# buckler.net
KiCad netlist of a schematic drawn in EAGLE
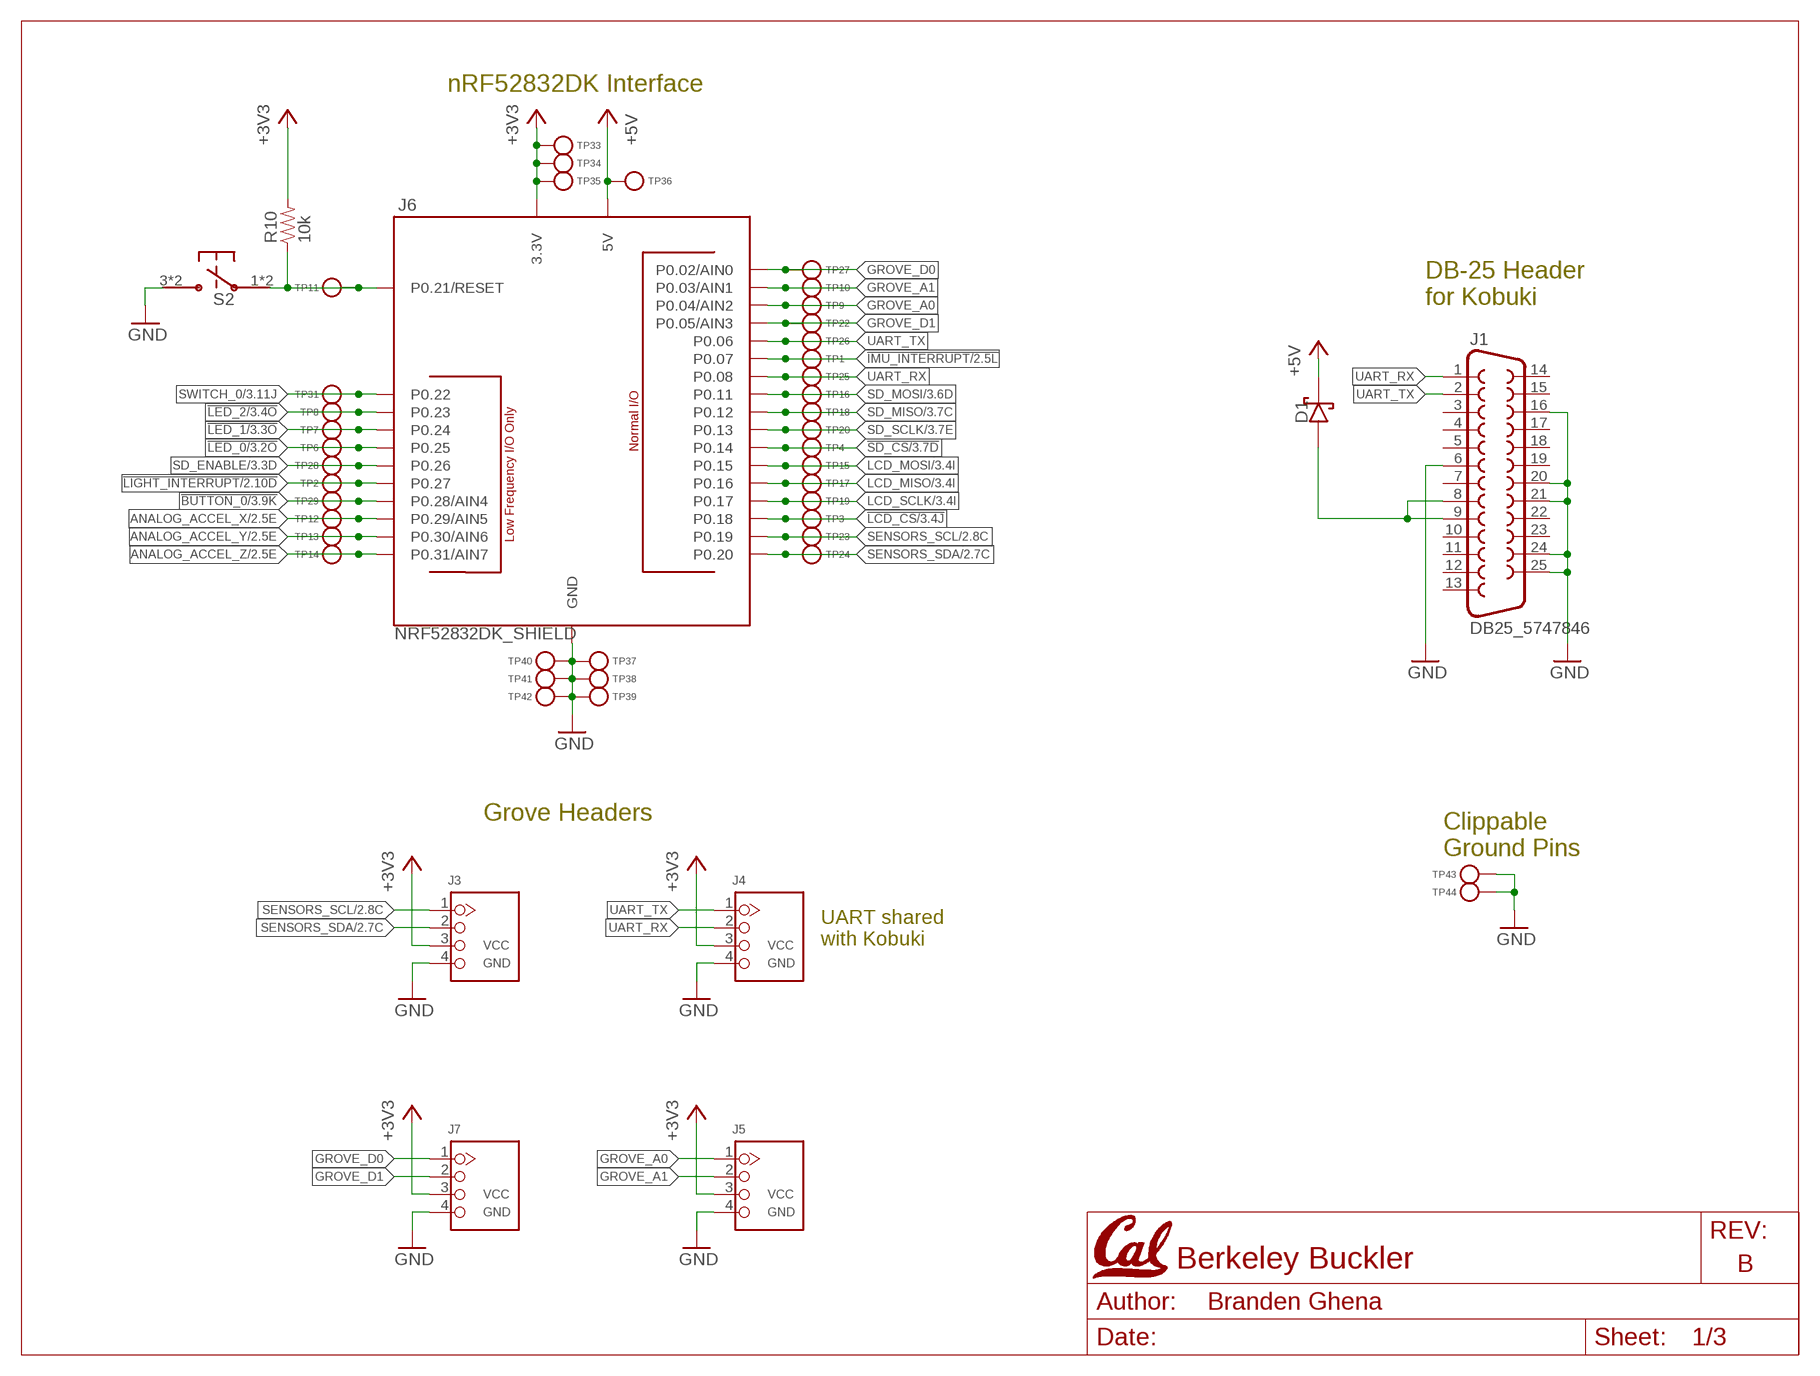
[diagram p0: schematic, sheet 1]
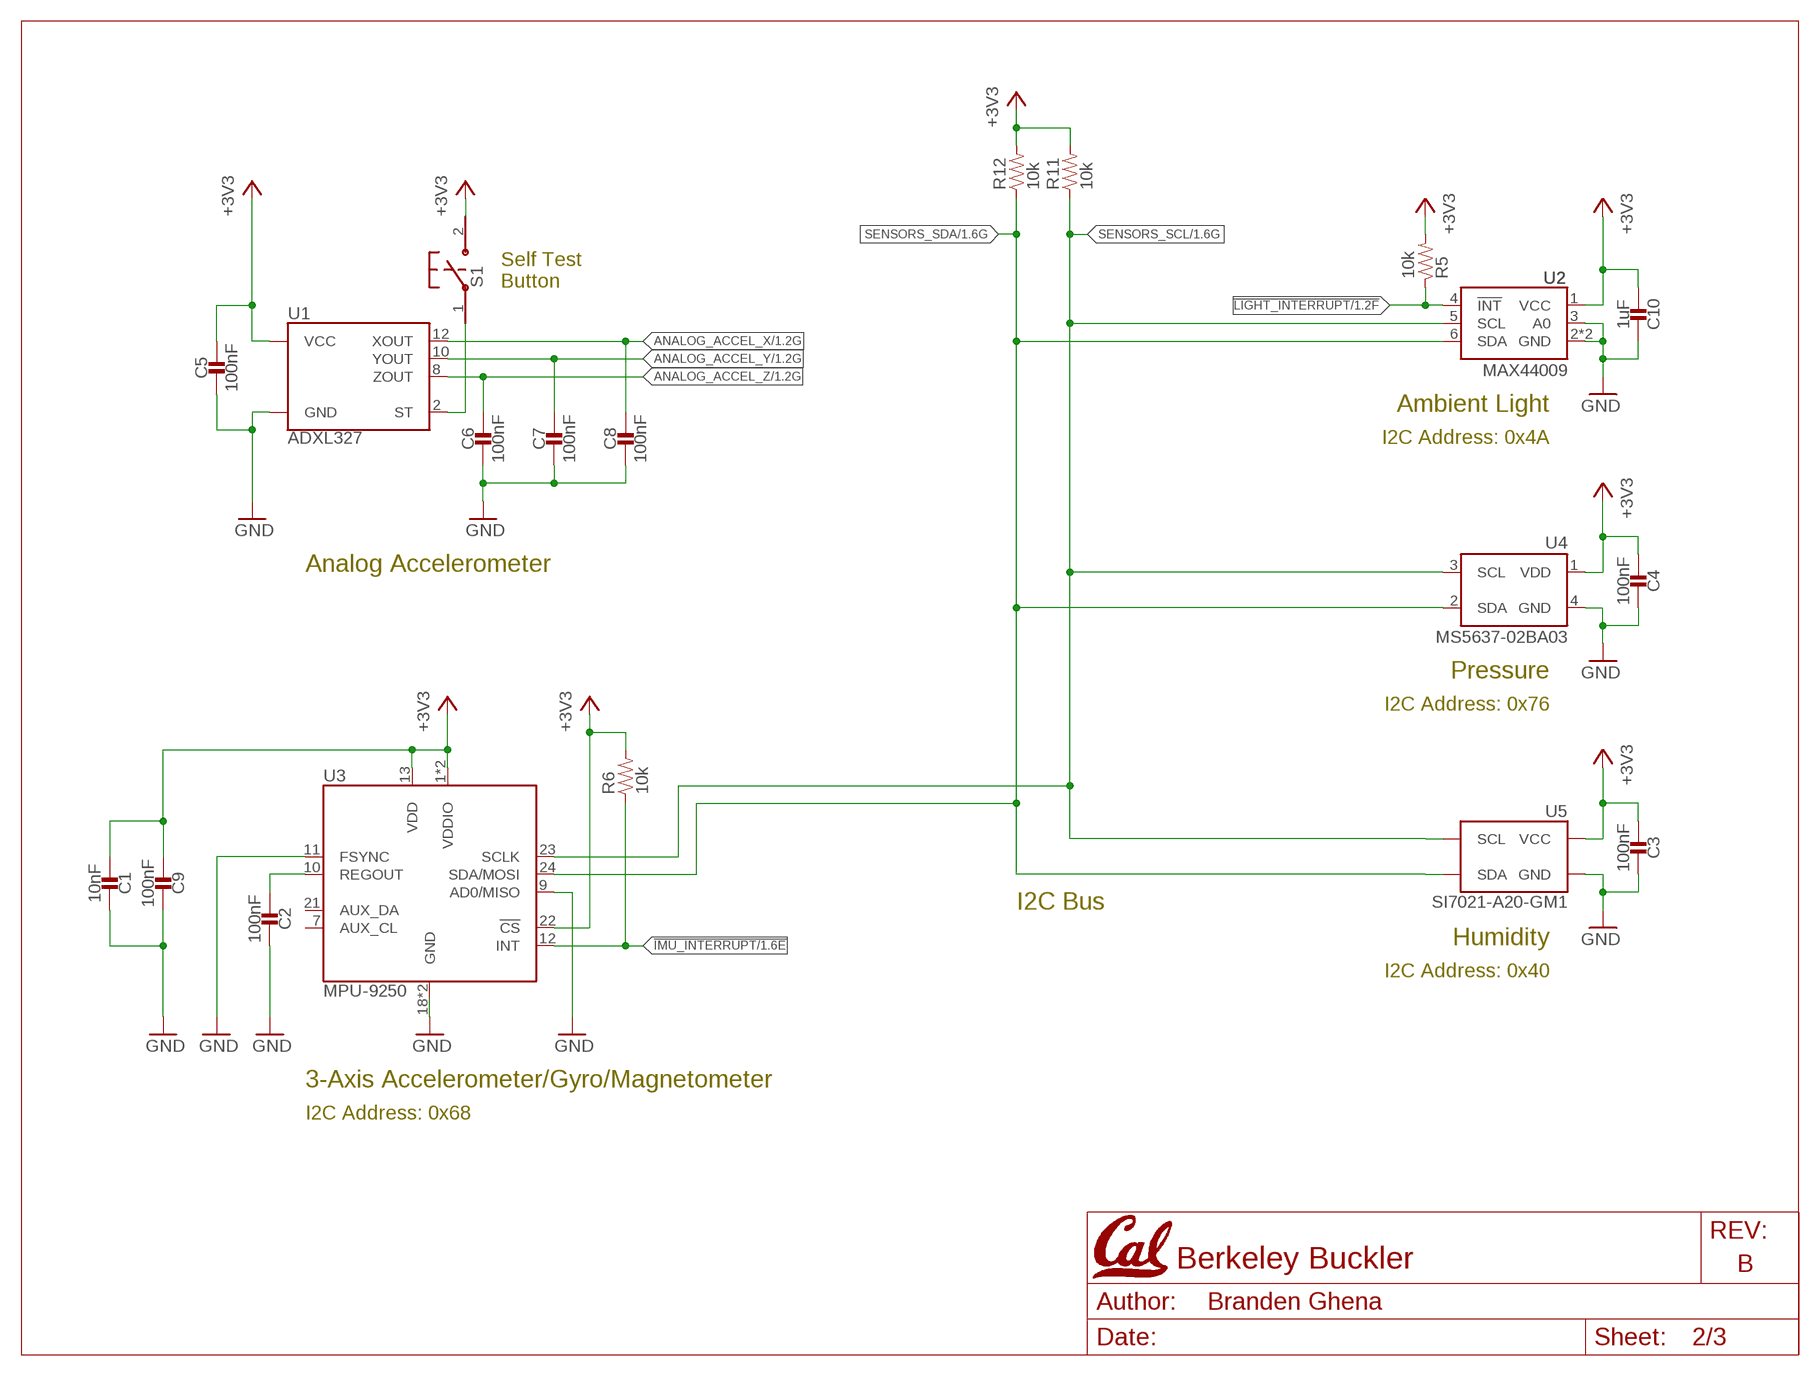
[diagram p1: schematic, sheet 2]
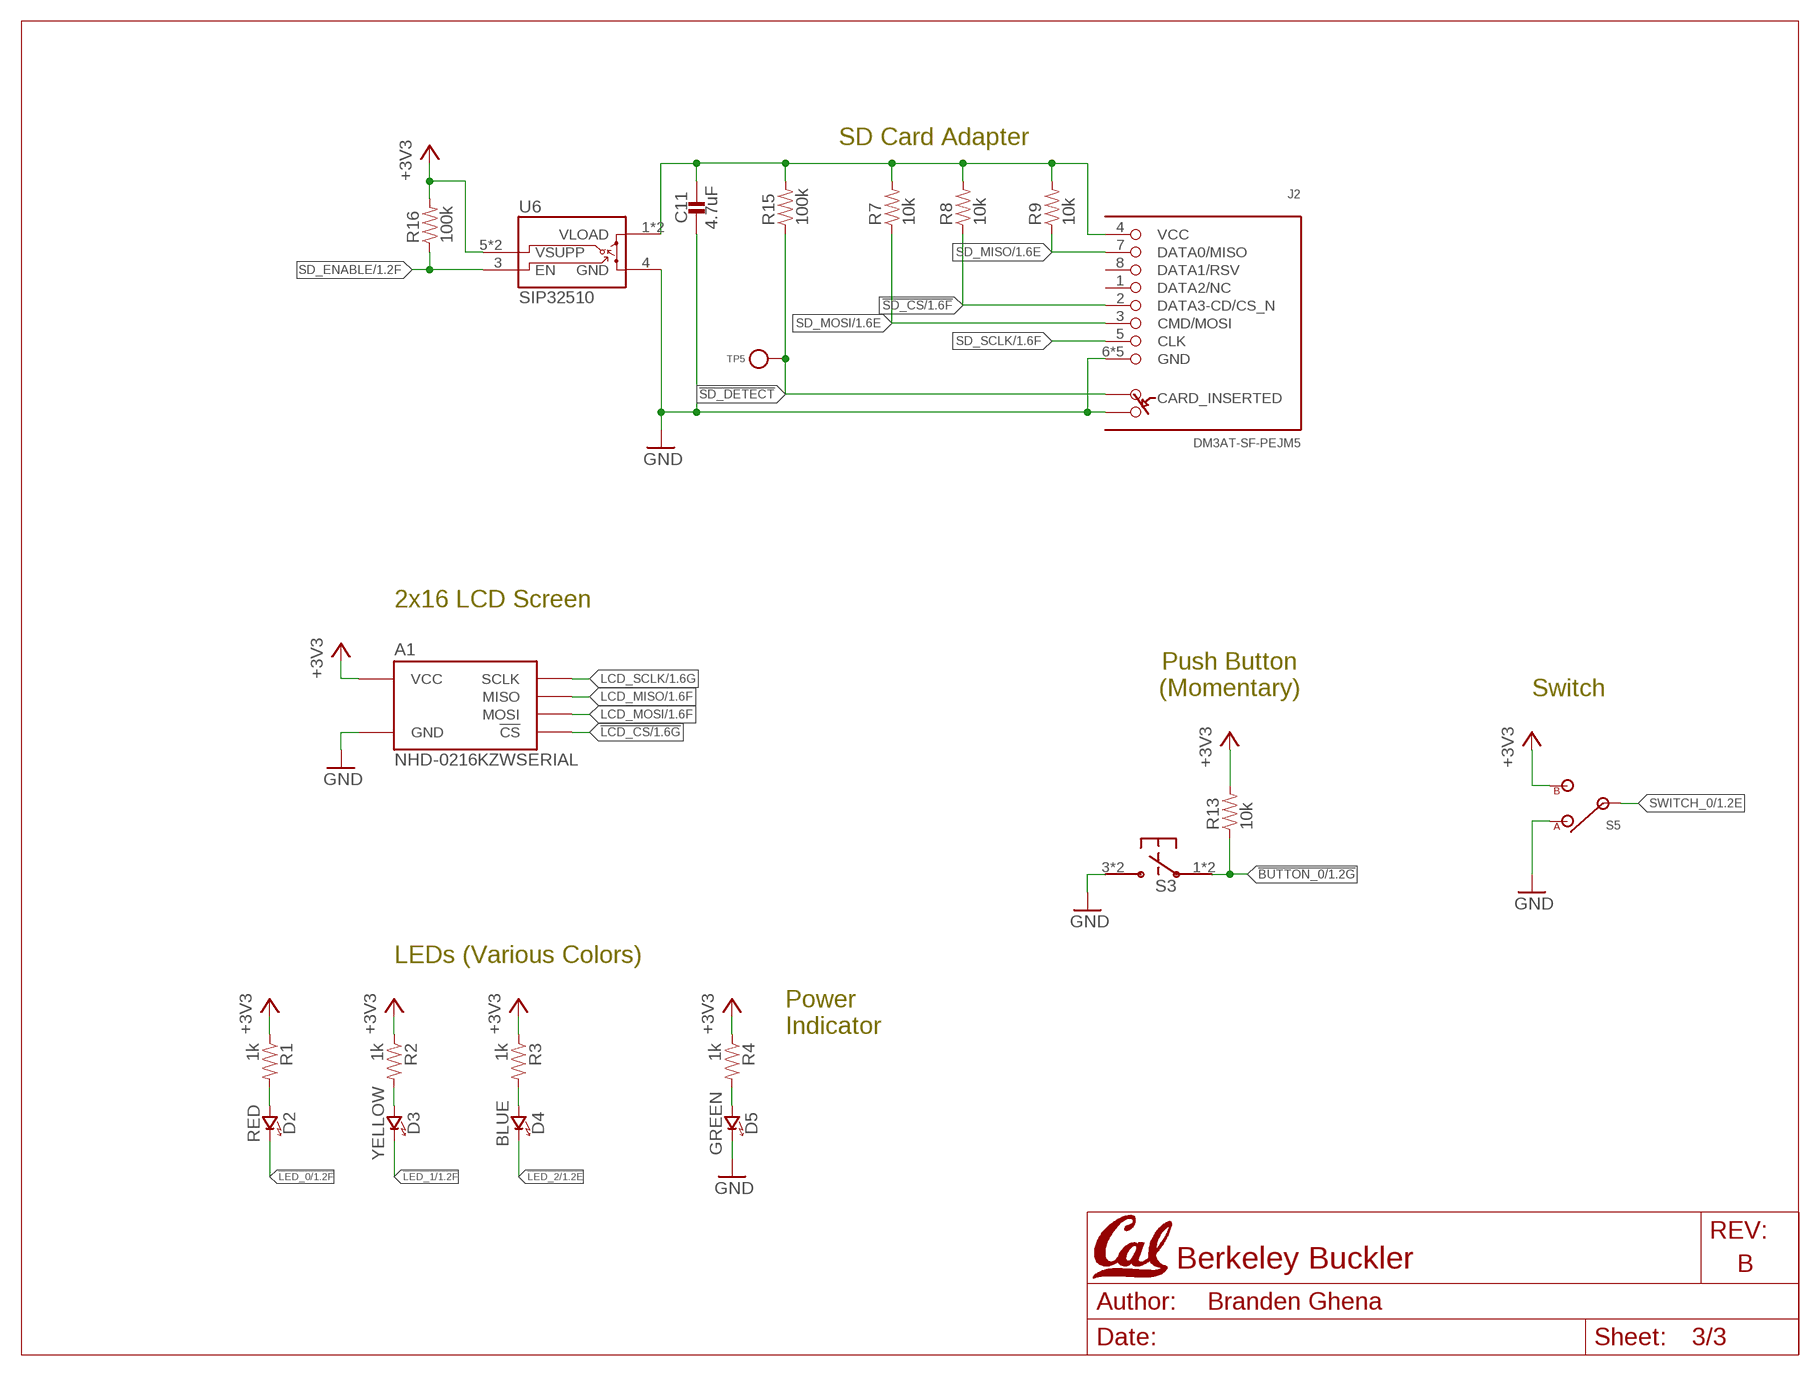
[diagram p2: schematic, sheet 3]

(export (version "E")
  (design (tool "Eeschema 10.0.6"))
  (components
    (comp (ref "C1")
      (value "10nF")
      (footprint "eagle-import:0402_CAP")
      (description "CAP CER 10000PF 25V X7R 0402")
      (fields (field (name "MANUFACTURER") "KEMET") (field (name "MPN") "C0402C103J3RACTU"))
      (libsource (lib "eagle-import") (part "CAPACITOR0402_CAP"))
    )
    (comp (ref "C2")
      (value "100nF")
      (footprint "eagle-import:0402_CAP")
      (description "CAP CER 0.1UF 16V X7R 0402")
      (fields (field (name "MANUFACTURER") "Murata") (field (name "MPN") "GCM155R71C104KA55D"))
      (libsource (lib "eagle-import") (part "CAPACITOR0402_CAP"))
    )
    (comp (ref "C3")
      (value "100nF")
      (footprint "eagle-import:0402_CAP")
      (description "CAP CER 0.1UF 16V X7R 0402")
      (fields (field (name "MANUFACTURER") "Murata") (field (name "MPN") "GCM155R71C104KA55D"))
      (libsource (lib "eagle-import") (part "CAPACITOR0402_CAP"))
    )
    (comp (ref "C4")
      (value "100nF")
      (footprint "eagle-import:0402_CAP")
      (description "CAP CER 0.1UF 16V X7R 0402")
      (fields (field (name "MANUFACTURER") "Murata") (field (name "MPN") "GCM155R71C104KA55D"))
      (libsource (lib "eagle-import") (part "CAPACITOR0402_CAP"))
    )
    (comp (ref "C5")
      (value "100nF")
      (footprint "eagle-import:0402_CAP")
      (description "CAP CER 0.1UF 16V X7R 0402")
      (fields (field (name "MANUFACTURER") "Murata") (field (name "MPN") "GCM155R71C104KA55D"))
      (libsource (lib "eagle-import") (part "CAPACITOR0402_CAP"))
    )
    (comp (ref "C6")
      (value "100nF")
      (footprint "eagle-import:0402_CAP")
      (description "CAP CER 0.1UF 16V X7R 0402")
      (fields (field (name "MANUFACTURER") "Murata") (field (name "MPN") "GCM155R71C104KA55D"))
      (libsource (lib "eagle-import") (part "CAPACITOR0402_CAP"))
    )
    (comp (ref "C7")
      (value "100nF")
      (footprint "eagle-import:0402_CAP")
      (description "CAP CER 0.1UF 16V X7R 0402")
      (fields (field (name "MANUFACTURER") "Murata") (field (name "MPN") "GCM155R71C104KA55D"))
      (libsource (lib "eagle-import") (part "CAPACITOR0402_CAP"))
    )
    (comp (ref "C8")
      (value "100nF")
      (footprint "eagle-import:0402_CAP")
      (description "CAP CER 0.1UF 16V X7R 0402")
      (fields (field (name "MANUFACTURER") "Murata") (field (name "MPN") "GCM155R71C104KA55D"))
      (libsource (lib "eagle-import") (part "CAPACITOR0402_CAP"))
    )
    (comp (ref "C9")
      (value "100nF")
      (footprint "eagle-import:0402_CAP")
      (description "CAP CER 0.1UF 16V X7R 0402")
      (fields (field (name "MANUFACTURER") "Murata") (field (name "MPN") "GCM155R71C104KA55D"))
      (libsource (lib "eagle-import") (part "CAPACITOR0402_CAP"))
    )
    (comp (ref "C10")
      (value "1uF")
      (footprint "eagle-import:0402_CAP")
      (description "CAP CER 1UF 10V X6S 0402")
      (fields
        (field (name "MANUFACTURER") "Samsung Electro-Mechanics")
        (field (name "MPN") "CL05X105KP5NNNC")
      )
      (libsource (lib "eagle-import") (part "CAPACITOR0402_CAP"))
    )
    (comp (ref "R5")
      (value "10k")
      (footprint "eagle-import:0402_RES")
      (description "RES SMD 10K OHM 1% 1/16W 0402")
      (fields (field (name "MANUFACTURER") "Samsung Electro-Mechanics") (field (name "MPN") "RC1005F103CS"))
      (libsource (lib "eagle-import") (part "RESISTOR0402_RES"))
    )
    (comp (ref "R6")
      (value "10k")
      (footprint "eagle-import:0402_RES")
      (description "RES SMD 10K OHM 1% 1/16W 0402")
      (fields (field (name "MANUFACTURER") "Samsung Electro-Mechanics") (field (name "MPN") "RC1005F103CS"))
      (libsource (lib "eagle-import") (part "RESISTOR0402_RES"))
    )
    (comp (ref "R11")
      (value "10k")
      (footprint "eagle-import:0402_RES")
      (description "RES SMD 10K OHM 1% 1/16W 0402")
      (fields (field (name "MANUFACTURER") "Samsung Electro-Mechanics") (field (name "MPN") "RC1005F103CS"))
      (libsource (lib "eagle-import") (part "RESISTOR0402_RES"))
    )
    (comp (ref "R12")
      (value "10k")
      (footprint "eagle-import:0402_RES")
      (description "RES SMD 10K OHM 1% 1/16W 0402")
      (fields (field (name "MANUFACTURER") "Samsung Electro-Mechanics") (field (name "MPN") "RC1005F103CS"))
      (libsource (lib "eagle-import") (part "RESISTOR0402_RES"))
    )
    (comp (ref "S1")
      (value "B3U-1000P")
      (footprint "eagle-import:B3U-1000P")
      (description "SWITCH TACTILE SPST-NO 0.05A 12V")
      (fields (field (name "MANUFACTURER") "Omron") (field (name "MPN") "B3U-1000P"))
      (libsource (lib "eagle-import") (part "B3U-1000P"))
    )
    (comp (ref "U1")
      (value "ADXL327")
      (footprint "eagle-import:LFCSP-16")
      (description "ACCELEROMETER 2G ANALOG 16LFCSP")
      (fields (field (name "MANUFACTURER") "Analog Devices Inc.") (field (name "MPN") "ADXL327BCPZ"))
      (libsource (lib "eagle-import") (part "ADXL327"))
    )
    (comp (ref "U2")
      (value "MAX44009")
      (footprint "eagle-import:UDFN-6-EXPOSED")
      (description "SENSOR AMBIENT LIGHT 6UTDFN")
      (fields
        (field (name "MANUFACTURER") "MAXIM")
        (field (name "MPN") "MAX44009EDT+T")
        (field (name "MANUFACTURER_1") "Maxim Integrated")
      )
      (libsource (lib "eagle-import") (part "MAX44009"))
    )
    (comp (ref "U3")
      (value "MPU-9250")
      (footprint "eagle-import:QFN-24_3MM")
      (description "IMU ACCEL/GYRO/MAG I2C/SPI 24QFN")
      (fields (field (name "MANUFACTURER") "TDK InvenSense"))
      (libsource (lib "eagle-import") (part "MPU-9250"))
    )
    (comp (ref "U4")
      (value "MS5637-02BA03")
      (footprint "eagle-import:4-SMD")
      (description "SENSOR 17.4PSIA I2C 24B 4-QFN")
      (fields (field (name "MANUFACTURER") "TE CONNECTIVITY") (field (name "MPN") "MS563702BA03-50"))
      (libsource (lib "eagle-import") (part "MS5637-02BA03"))
    )
    (comp (ref "U5")
      (value "SI7021-A20-GM1")
      (footprint "eagle-import:DFN-6_3MM")
      (description "SENS HUMI/TEMP 3.6V I2C 3% 6DFN")
      (fields (field (name "MANUFACTURER") "Silicon Labs") (field (name "MPN") "SI7021-A20-GM1 "))
      (libsource (lib "eagle-import") (part "SI7021-A20-GM1"))
    )
    (comp (ref "D1")
      (value "DIODE_SCHOTTKYSOD323")
      (footprint "eagle-import:SOD323")
      (description "DIODE SCHOTTKY 30V 500MA SOD323")
      (fields (field (name "MANUFACTURER") "Diodes Incorporated") (field (name "MPN") "B0530WS-7-F"))
      (libsource (lib "eagle-import") (part "DIODE_SCHOTTKYSOD323"))
    )
    (comp (ref "J1")
      (value "DB25_5747846")
      (footprint "eagle-import:DB25_5747846")
      (description "CONN D-SUB RCPT 25POS R/A SOLDER")
      (fields (field (name "MANUFACTURER") "TE Connectivity AMP Connectors") (field (name "MPN") "5747846-4"))
      (libsource (lib "eagle-import") (part "DB25_5747846"))
    )
    (comp (ref "J3")
      (value "4P-2.0")
      (footprint "eagle-import:HW4-2.0")
      (description "Grove - Universal 4 pin connector")
      (fields (field (name "MANUFACTURER") "Seeed Studio") (field (name "MPN") "110990030"))
      (libsource (lib "eagle-import") (part "GROVE-CONNECTOR-DIP(4P-2.0)"))
    )
    (comp (ref "J4")
      (value "4P-2.0")
      (footprint "eagle-import:HW4-2.0")
      (description "Grove - Universal 4 pin connector")
      (fields (field (name "MANUFACTURER") "Seeed Studio") (field (name "MPN") "110990030"))
      (libsource (lib "eagle-import") (part "GROVE-CONNECTOR-DIP(4P-2.0)"))
    )
    (comp (ref "J5")
      (value "4P-2.0")
      (footprint "eagle-import:HW4-2.0")
      (description "Grove - Universal 4 pin connector")
      (fields (field (name "MANUFACTURER") "Seeed Studio") (field (name "MPN") "110990030"))
      (libsource (lib "eagle-import") (part "GROVE-CONNECTOR-DIP(4P-2.0)"))
    )
    (comp (ref "J6")
      (value "NRF52832DK_SHIELD")
      (footprint "eagle-import:NRF52832DK_SHIELD")
      (libsource (lib "eagle-import") (part "NRF52832DK_SHIELD"))
    )
    (comp (ref "J7")
      (value "4P-2.0")
      (footprint "eagle-import:HW4-2.0")
      (description "Grove - Universal 4 pin connector")
      (fields (field (name "MANUFACTURER") "Seeed Studio") (field (name "MPN") "110990030"))
      (libsource (lib "eagle-import") (part "GROVE-CONNECTOR-DIP(4P-2.0)"))
    )
    (comp (ref "R10")
      (value "10k")
      (footprint "eagle-import:0402_RES")
      (description "RES SMD 10K OHM 1% 1/16W 0402")
      (fields (field (name "MANUFACTURER") "Samsung Electro-Mechanics") (field (name "MPN") "RC1005F103CS"))
      (libsource (lib "eagle-import") (part "RESISTOR0402_RES"))
    )
    (comp (ref "S2")
      (value "PTS645SM43SMTR92")
      (footprint "eagle-import:PTS645")
      (description "SWITCH TACTILE SPST-NO 0.05A 12V")
      (fields (field (name "MANUFACTURER") "C&K") (field (name "MPN") "PTS645SM43SMTR92 LFS"))
      (libsource (lib "eagle-import") (part "PTS645SM43SMTR92"))
    )
    (comp (ref "TP1")
      (value "TEST_POINT_0.040IN")
      (footprint "eagle-import:TESTPOINT_0.040IN")
      (libsource (lib "eagle-import") (part "TEST_POINT_0.040IN"))
    )
    (comp (ref "TP2")
      (value "TEST_POINT_0.040IN")
      (footprint "eagle-import:TESTPOINT_0.040IN")
      (libsource (lib "eagle-import") (part "TEST_POINT_0.040IN"))
    )
    (comp (ref "TP3")
      (value "TEST_POINT_0.040IN")
      (footprint "eagle-import:TESTPOINT_0.040IN")
      (libsource (lib "eagle-import") (part "TEST_POINT_0.040IN"))
    )
    (comp (ref "TP4")
      (value "TEST_POINT_0.040IN")
      (footprint "eagle-import:TESTPOINT_0.040IN")
      (libsource (lib "eagle-import") (part "TEST_POINT_0.040IN"))
    )
    (comp (ref "TP6")
      (value "TEST_POINT_0.040IN")
      (footprint "eagle-import:TESTPOINT_0.040IN")
      (libsource (lib "eagle-import") (part "TEST_POINT_0.040IN"))
    )
    (comp (ref "TP7")
      (value "TEST_POINT_0.040IN")
      (footprint "eagle-import:TESTPOINT_0.040IN")
      (libsource (lib "eagle-import") (part "TEST_POINT_0.040IN"))
    )
    (comp (ref "TP8")
      (value "TEST_POINT_0.040IN")
      (footprint "eagle-import:TESTPOINT_0.040IN")
      (libsource (lib "eagle-import") (part "TEST_POINT_0.040IN"))
    )
    (comp (ref "TP9")
      (value "TEST_POINT_0.040IN")
      (footprint "eagle-import:TESTPOINT_0.040IN")
      (libsource (lib "eagle-import") (part "TEST_POINT_0.040IN"))
    )
    (comp (ref "TP10")
      (value "TEST_POINT_0.040IN")
      (footprint "eagle-import:TESTPOINT_0.040IN")
      (libsource (lib "eagle-import") (part "TEST_POINT_0.040IN"))
    )
    (comp (ref "TP11")
      (value "TEST_POINT_0.040IN")
      (footprint "eagle-import:TESTPOINT_0.040IN")
      (libsource (lib "eagle-import") (part "TEST_POINT_0.040IN"))
    )
    (comp (ref "TP12")
      (value "TEST_POINT_0.040IN")
      (footprint "eagle-import:TESTPOINT_0.040IN")
      (libsource (lib "eagle-import") (part "TEST_POINT_0.040IN"))
    )
    (comp (ref "TP13")
      (value "TEST_POINT_0.040IN")
      (footprint "eagle-import:TESTPOINT_0.040IN")
      (libsource (lib "eagle-import") (part "TEST_POINT_0.040IN"))
    )
    (comp (ref "TP14")
      (value "TEST_POINT_0.040IN")
      (footprint "eagle-import:TESTPOINT_0.040IN")
      (libsource (lib "eagle-import") (part "TEST_POINT_0.040IN"))
    )
    (comp (ref "TP15")
      (value "TEST_POINT_0.040IN")
      (footprint "eagle-import:TESTPOINT_0.040IN")
      (libsource (lib "eagle-import") (part "TEST_POINT_0.040IN"))
    )
    (comp (ref "TP16")
      (value "TEST_POINT_0.040IN")
      (footprint "eagle-import:TESTPOINT_0.040IN")
      (libsource (lib "eagle-import") (part "TEST_POINT_0.040IN"))
    )
    (comp (ref "TP17")
      (value "TEST_POINT_0.040IN")
      (footprint "eagle-import:TESTPOINT_0.040IN")
      (libsource (lib "eagle-import") (part "TEST_POINT_0.040IN"))
    )
    (comp (ref "TP18")
      (value "TEST_POINT_0.040IN")
      (footprint "eagle-import:TESTPOINT_0.040IN")
      (libsource (lib "eagle-import") (part "TEST_POINT_0.040IN"))
    )
    (comp (ref "TP19")
      (value "TEST_POINT_0.040IN")
      (footprint "eagle-import:TESTPOINT_0.040IN")
      (libsource (lib "eagle-import") (part "TEST_POINT_0.040IN"))
    )
    (comp (ref "TP20")
      (value "TEST_POINT_0.040IN")
      (footprint "eagle-import:TESTPOINT_0.040IN")
      (libsource (lib "eagle-import") (part "TEST_POINT_0.040IN"))
    )
    (comp (ref "TP22")
      (value "TEST_POINT_0.040IN")
      (footprint "eagle-import:TESTPOINT_0.040IN")
      (libsource (lib "eagle-import") (part "TEST_POINT_0.040IN"))
    )
    (comp (ref "TP23")
      (value "TEST_POINT_0.040IN")
      (footprint "eagle-import:TESTPOINT_0.040IN")
      (libsource (lib "eagle-import") (part "TEST_POINT_0.040IN"))
    )
    (comp (ref "TP24")
      (value "TEST_POINT_0.040IN")
      (footprint "eagle-import:TESTPOINT_0.040IN")
      (libsource (lib "eagle-import") (part "TEST_POINT_0.040IN"))
    )
    (comp (ref "TP25")
      (value "TEST_POINT_0.040IN")
      (footprint "eagle-import:TESTPOINT_0.040IN")
      (libsource (lib "eagle-import") (part "TEST_POINT_0.040IN"))
    )
    (comp (ref "TP26")
      (value "TEST_POINT_0.040IN")
      (footprint "eagle-import:TESTPOINT_0.040IN")
      (libsource (lib "eagle-import") (part "TEST_POINT_0.040IN"))
    )
    (comp (ref "TP27")
      (value "TEST_POINT_0.040IN")
      (footprint "eagle-import:TESTPOINT_0.040IN")
      (libsource (lib "eagle-import") (part "TEST_POINT_0.040IN"))
    )
    (comp (ref "TP28")
      (value "TEST_POINT_0.040IN")
      (footprint "eagle-import:TESTPOINT_0.040IN")
      (libsource (lib "eagle-import") (part "TEST_POINT_0.040IN"))
    )
    (comp (ref "TP29")
      (value "TEST_POINT_0.040IN")
      (footprint "eagle-import:TESTPOINT_0.040IN")
      (libsource (lib "eagle-import") (part "TEST_POINT_0.040IN"))
    )
    (comp (ref "TP31")
      (value "TEST_POINT_0.040IN")
      (footprint "eagle-import:TESTPOINT_0.040IN")
      (libsource (lib "eagle-import") (part "TEST_POINT_0.040IN"))
    )
    (comp (ref "TP33")
      (value "TEST_POINT_0.040IN")
      (footprint "eagle-import:TESTPOINT_0.040IN")
      (libsource (lib "eagle-import") (part "TEST_POINT_0.040IN"))
    )
    (comp (ref "TP34")
      (value "TEST_POINT_0.040IN")
      (footprint "eagle-import:TESTPOINT_0.040IN")
      (libsource (lib "eagle-import") (part "TEST_POINT_0.040IN"))
    )
    (comp (ref "TP35")
      (value "TEST_POINT_0.040IN")
      (footprint "eagle-import:TESTPOINT_0.040IN")
      (libsource (lib "eagle-import") (part "TEST_POINT_0.040IN"))
    )
    (comp (ref "TP36")
      (value "TEST_POINT_0.040IN")
      (footprint "eagle-import:TESTPOINT_0.040IN")
      (libsource (lib "eagle-import") (part "TEST_POINT_0.040IN"))
    )
    (comp (ref "TP37")
      (value "TEST_POINT_0.040IN")
      (footprint "eagle-import:TESTPOINT_0.040IN")
      (libsource (lib "eagle-import") (part "TEST_POINT_0.040IN"))
    )
    (comp (ref "TP38")
      (value "TEST_POINT_0.040IN")
      (footprint "eagle-import:TESTPOINT_0.040IN")
      (libsource (lib "eagle-import") (part "TEST_POINT_0.040IN"))
    )
    (comp (ref "TP39")
      (value "TEST_POINT_0.040IN")
      (footprint "eagle-import:TESTPOINT_0.040IN")
      (libsource (lib "eagle-import") (part "TEST_POINT_0.040IN"))
    )
    (comp (ref "TP40")
      (value "TEST_POINT_0.040IN")
      (footprint "eagle-import:TESTPOINT_0.040IN")
      (libsource (lib "eagle-import") (part "TEST_POINT_0.040IN"))
    )
    (comp (ref "TP41")
      (value "TEST_POINT_0.040IN")
      (footprint "eagle-import:TESTPOINT_0.040IN")
      (libsource (lib "eagle-import") (part "TEST_POINT_0.040IN"))
    )
    (comp (ref "TP42")
      (value "TEST_POINT_0.040IN")
      (footprint "eagle-import:TESTPOINT_0.040IN")
      (libsource (lib "eagle-import") (part "TEST_POINT_0.040IN"))
    )
    (comp (ref "TP43")
      (value "TEST_POINT_0.078IN")
      (footprint "eagle-import:TESTPOINT_0.078IN")
      (description "TERM TURRET SINGLE L=4.75MM TIN")
      (fields (field (name "MANUFACTURER") "Keystone Electronics") (field (name "MPN") "1520-2"))
      (libsource (lib "eagle-import") (part "TEST_POINT_0.078IN"))
    )
    (comp (ref "TP44")
      (value "TEST_POINT_0.078IN")
      (footprint "eagle-import:TESTPOINT_0.078IN")
      (description "TERM TURRET SINGLE L=4.75MM TIN")
      (fields (field (name "MANUFACTURER") "Keystone Electronics") (field (name "MPN") "1520-2"))
      (libsource (lib "eagle-import") (part "TEST_POINT_0.078IN"))
    )
    (comp (ref "A1")
      (value "NHD-0216KZWSERIAL")
      (footprint "eagle-import:NHD-0216KZW")
      (libsource (lib "eagle-import") (part "NHD-0216KZWSERIAL"))
    )
    (comp (ref "C11")
      (value "4.7uF")
      (footprint "eagle-import:0402_CAP")
      (description "CAP CER 4.7UF 10V X5R 0402")
      (fields
        (field (name "MANUFACTURER") "Samsung Electro-Mechanics")
        (field (name "MPN") "CL05A475KP5NRNC")
      )
      (libsource (lib "eagle-import") (part "CAPACITOR0402_CAP"))
    )
    (comp (ref "D2")
      (value "RED")
      (footprint "eagle-import:LED-0603")
      (description "LED RED CLEAR CHIP SMD")
      (fields (field (name "MANUFACTURER") "Lite-On Inc.") (field (name "MPN") "LTST-C190KRKT"))
      (libsource (lib "eagle-import") (part "LED0603"))
    )
    (comp (ref "D3")
      (value "YELLOW")
      (footprint "eagle-import:LED-0603")
      (description "LED YELLOW CLEAR CHIP SMD")
      (fields (field (name "MANUFACTURER") "Lite-On Inc.") (field (name "MPN") "LTST-C190KSKT"))
      (libsource (lib "eagle-import") (part "LED0603"))
    )
    (comp (ref "D4")
      (value "BLUE")
      (footprint "eagle-import:LED-0603")
      (description "LED BLUE CLEAR SMD")
      (fields (field (name "MANUFACTURER") "Lite-On Inc.") (field (name "MPN") "LTST-C194TBKT"))
      (libsource (lib "eagle-import") (part "LED0603"))
    )
    (comp (ref "D5")
      (value "GREEN")
      (footprint "eagle-import:LED-0603")
      (description "LED GREEN CLEAR CHIP SMD")
      (fields (field (name "MANUFACTURER") "Lite-On Inc.") (field (name "MPN") "LTST-C190KGKT"))
      (libsource (lib "eagle-import") (part "LED0603"))
    )
    (comp (ref "J2")
      (value "DM3AT-SF-PEJM5")
      (footprint "eagle-import:DM3AT-SF-PEJM5")
      (fields (field (name "MANUFACTURER") "Hirose Electric Co Ltd"))
      (libsource (lib "eagle-import") (part "DM3AT-SF-PEJM5"))
    )
    (comp (ref "R1")
      (value "1k")
      (footprint "eagle-import:0402_RES")
      (description "RES SMD 1K OHM 1% 1/16W 0402")
      (fields (field (name "MANUFACTURER") "Stackpole Electronics") (field (name "MPN") "RMCF0402FT1K00"))
      (libsource (lib "eagle-import") (part "RESISTOR0402_RES"))
    )
    (comp (ref "R2")
      (value "1k")
      (footprint "eagle-import:0402_RES")
      (description "RES SMD 1K OHM 1% 1/16W 0402")
      (fields (field (name "MANUFACTURER") "Stackpole Electronics") (field (name "MPN") "RMCF0402FT1K00"))
      (libsource (lib "eagle-import") (part "RESISTOR0402_RES"))
    )
    (comp (ref "R3")
      (value "1k")
      (footprint "eagle-import:0402_RES")
      (description "RES SMD 1K OHM 1% 1/16W 0402")
      (fields (field (name "MANUFACTURER") "Stackpole Electronics") (field (name "MPN") "RMCF0402FT1K00"))
      (libsource (lib "eagle-import") (part "RESISTOR0402_RES"))
    )
    (comp (ref "R4")
      (value "1k")
      (footprint "eagle-import:0402_RES")
      (description "RES SMD 1K OHM 1% 1/16W 0402")
      (fields (field (name "MANUFACTURER") "Stackpole Electronics") (field (name "MPN") "RMCF0402FT1K00"))
      (libsource (lib "eagle-import") (part "RESISTOR0402_RES"))
    )
    (comp (ref "R7")
      (value "10k")
      (footprint "eagle-import:0402_RES")
      (description "RES SMD 10K OHM 1% 1/16W 0402")
      (fields (field (name "MANUFACTURER") "Samsung Electro-Mechanics") (field (name "MPN") "RC1005F103CS"))
      (libsource (lib "eagle-import") (part "RESISTOR0402_RES"))
    )
    (comp (ref "R8")
      (value "10k")
      (footprint "eagle-import:0402_RES")
      (description "RES SMD 10K OHM 1% 1/16W 0402")
      (fields (field (name "MANUFACTURER") "Samsung Electro-Mechanics") (field (name "MPN") "RC1005F103CS"))
      (libsource (lib "eagle-import") (part "RESISTOR0402_RES"))
    )
    (comp (ref "R9")
      (value "10k")
      (footprint "eagle-import:0402_RES")
      (description "RES SMD 10K OHM 1% 1/16W 0402")
      (fields (field (name "MANUFACTURER") "Samsung Electro-Mechanics") (field (name "MPN") "RC1005F103CS"))
      (libsource (lib "eagle-import") (part "RESISTOR0402_RES"))
    )
    (comp (ref "R13")
      (value "10k")
      (footprint "eagle-import:0402_RES")
      (description "RES SMD 10K OHM 1% 1/16W 0402")
      (fields (field (name "MANUFACTURER") "Samsung Electro-Mechanics") (field (name "MPN") "RC1005F103CS"))
      (libsource (lib "eagle-import") (part "RESISTOR0402_RES"))
    )
    (comp (ref "R15")
      (value "100k")
      (footprint "eagle-import:0402_RES")
      (description "RES SMD 100K OHM 1% 1/5W 0402")
      (fields (field (name "MANUFACTURER") "Vishay Dale") (field (name "MPN") "CRCW0402100KFKEDHP"))
      (libsource (lib "eagle-import") (part "RESISTOR0402_RES"))
    )
    (comp (ref "R16")
      (value "100k")
      (footprint "eagle-import:0402_RES")
      (description "RES SMD 100K OHM 1% 1/5W 0402")
      (fields (field (name "MANUFACTURER") "Vishay Dale") (field (name "MPN") "CRCW0402100KFKEDHP"))
      (libsource (lib "eagle-import") (part "RESISTOR0402_RES"))
    )
    (comp (ref "S3")
      (value "PTS645SM43SMTR92")
      (footprint "eagle-import:PTS645")
      (description "SWITCH TACTILE SPST-NO 0.05A 12V")
      (fields (field (name "MANUFACTURER") "C&K") (field (name "MPN") "PTS645SM43SMTR92 LFS"))
      (libsource (lib "eagle-import") (part "PTS645SM43SMTR92"))
    )
    (comp (ref "S5")
      (value "TE_SSA12/SPDT")
      (footprint "eagle-import:TE_SSA12_SPDT")
      (description "SWITCH SLIDE SPDT 100MA 30V")
      (fields
        (field (name "MANUFACTURER") "TE Connectivity ALCOSWITCH Switches")
        (field (name "MPN") "SSA12")
      )
      (libsource (lib "eagle-import") (part "TE_SSA12/SPDT"))
    )
    (comp (ref "TP5")
      (value "TEST_POINT_0.040IN")
      (footprint "eagle-import:TESTPOINT_0.040IN")
      (libsource (lib "eagle-import") (part "TEST_POINT_0.040IN"))
    )
    (comp (ref "U6")
      (value "SIP32510")
      (footprint "eagle-import:TSOT23-6")
      (description "IC LOAD SWITCH SOT23-6")
      (fields (field (name "MANUFACTURER") "Vishay") (field (name "MPN") "SIP32510DT-T1-GE3"))
      (libsource (lib "eagle-import") (part "SIP32510"))
    )
  )
  (nets
    (net (code "1") (name "+3V3") (class "Default")
      (node (ref "A1") (pin "2") (pinfunction "VCC_2") (pintype "bidirectional"))
      (node (ref "C1") (pin "1") (pinfunction "1_1") (pintype "bidirectional"))
      (node (ref "C10") (pin "1") (pinfunction "1_1") (pintype "bidirectional"))
      (node (ref "C3") (pin "1") (pinfunction "1_1") (pintype "bidirectional"))
      (node (ref "C4") (pin "1") (pinfunction "1_1") (pintype "bidirectional"))
      (node (ref "C5") (pin "1") (pinfunction "1_1") (pintype "bidirectional"))
      (node (ref "C9") (pin "1") (pinfunction "1_1") (pintype "bidirectional"))
      (node (ref "J3") (pin "3") (pinfunction "3_3") (pintype "bidirectional"))
      (node (ref "J4") (pin "3") (pinfunction "3_3") (pintype "bidirectional"))
      (node (ref "J5") (pin "3") (pinfunction "3_3") (pintype "bidirectional"))
      (node (ref "J6") (pin "3.3V@0") (pinfunction "3.3V_3.3V@0") (pintype "bidirectional"))
      (node (ref "J6") (pin "3.3V@1") (pinfunction "3.3V_3.3V@1") (pintype "bidirectional"))
      (node (ref "J6") (pin "3.3V@2") (pinfunction "3.3V_3.3V@2") (pintype "bidirectional"))
      (node (ref "J7") (pin "3") (pinfunction "3_3") (pintype "bidirectional"))
      (node (ref "R1") (pin "1") (pinfunction "1_1") (pintype "passive"))
      (node (ref "R10") (pin "2") (pinfunction "2_2") (pintype "passive"))
      (node (ref "R11") (pin "2") (pinfunction "2_2") (pintype "passive"))
      (node (ref "R12") (pin "2") (pinfunction "2_2") (pintype "passive"))
      (node (ref "R13") (pin "2") (pinfunction "2_2") (pintype "passive"))
      (node (ref "R16") (pin "2") (pinfunction "2_2") (pintype "passive"))
      (node (ref "R2") (pin "1") (pinfunction "1_1") (pintype "passive"))
      (node (ref "R3") (pin "1") (pinfunction "1_1") (pintype "passive"))
      (node (ref "R4") (pin "1") (pinfunction "1_1") (pintype "passive"))
      (node (ref "R5") (pin "2") (pinfunction "2_2") (pintype "passive"))
      (node (ref "R6") (pin "2") (pinfunction "2_2") (pintype "passive"))
      (node (ref "S1") (pin "2") (pinfunction "P$2_2") (pintype "passive"))
      (node (ref "S5") (pin "2") (pinfunction "B_2") (pintype "bidirectional"))
      (node (ref "TP33") (pin "TESTPOINT") (pinfunction "TESTPOINT_TESTPOINT") (pintype "bidirectional"))
      (node (ref "TP34") (pin "TESTPOINT") (pinfunction "TESTPOINT_TESTPOINT") (pintype "bidirectional"))
      (node (ref "TP35") (pin "TESTPOINT") (pinfunction "TESTPOINT_TESTPOINT") (pintype "bidirectional"))
      (node (ref "U1") (pin "14") (pinfunction "VCC_14") (pintype "bidirectional"))
      (node (ref "U1") (pin "15") (pinfunction "VCC_15") (pintype "bidirectional"))
      (node (ref "U2") (pin "1") (pinfunction "VCC_1") (pintype "bidirectional"))
      (node (ref "U3") (pin "1") (pinfunction "VDDIO_1") (pintype "bidirectional"))
      (node (ref "U3") (pin "13") (pinfunction "VDD_13") (pintype "bidirectional"))
      (node (ref "U3") (pin "22") (pinfunction "~{CS}_22") (pintype "bidirectional"))
      (node (ref "U3") (pin "8") (pinfunction "VDDIO_8") (pintype "bidirectional"))
      (node (ref "U4") (pin "1") (pinfunction "VDD_1") (pintype "bidirectional"))
      (node (ref "U5") (pin "5") (pinfunction "VCC_5") (pintype "bidirectional"))
      (node (ref "U6") (pin "5") (pinfunction "VSUPP_5") (pintype "bidirectional"))
      (node (ref "U6") (pin "6") (pinfunction "VSUPP_6") (pintype "bidirectional"))
    )
    (net (code "2") (name "+5V") (class "Default")
      (node (ref "D1") (pin "P$1") (pinfunction "CATHODE_P$1") (pintype "bidirectional"))
      (node (ref "J6") (pin "5V") (pinfunction "5V_5V") (pintype "bidirectional"))
      (node (ref "TP36") (pin "TESTPOINT") (pinfunction "TESTPOINT_TESTPOINT") (pintype "bidirectional"))
    )
    (net (code "3") (name "ANALOG_ACCEL_X") (class "Default")
      (node (ref "C8") (pin "1") (pinfunction "1_1") (pintype "bidirectional"))
      (node (ref "J6") (pin "P0.29") (pinfunction "P0.29/AIN5_P0.29") (pintype "bidirectional"))
      (node (ref "TP12") (pin "TESTPOINT") (pinfunction "TESTPOINT_TESTPOINT") (pintype "bidirectional"))
      (node (ref "U1") (pin "12") (pinfunction "XOUT_12") (pintype "bidirectional"))
    )
    (net (code "4") (name "ANALOG_ACCEL_Y") (class "Default")
      (node (ref "C7") (pin "1") (pinfunction "1_1") (pintype "bidirectional"))
      (node (ref "J6") (pin "P0.30") (pinfunction "P0.30/AIN6_P0.30") (pintype "bidirectional"))
      (node (ref "TP13") (pin "TESTPOINT") (pinfunction "TESTPOINT_TESTPOINT") (pintype "bidirectional"))
      (node (ref "U1") (pin "10") (pinfunction "YOUT_10") (pintype "bidirectional"))
    )
    (net (code "5") (name "ANALOG_ACCEL_Z") (class "Default")
      (node (ref "C6") (pin "1") (pinfunction "1_1") (pintype "bidirectional"))
      (node (ref "J6") (pin "P0.31") (pinfunction "P0.31/AIN7_P0.31") (pintype "bidirectional"))
      (node (ref "TP14") (pin "TESTPOINT") (pinfunction "TESTPOINT_TESTPOINT") (pintype "bidirectional"))
      (node (ref "U1") (pin "8") (pinfunction "ZOUT_8") (pintype "bidirectional"))
    )
    (net (code "6") (name "GND") (class "Default")
      (node (ref "A1") (pin "1") (pinfunction "GND_1") (pintype "bidirectional"))
      (node (ref "C1") (pin "2") (pinfunction "2_2") (pintype "bidirectional"))
      (node (ref "C10") (pin "2") (pinfunction "2_2") (pintype "bidirectional"))
      (node (ref "C11") (pin "2") (pinfunction "2_2") (pintype "bidirectional"))
      (node (ref "C2") (pin "2") (pinfunction "2_2") (pintype "bidirectional"))
      (node (ref "C3") (pin "2") (pinfunction "2_2") (pintype "bidirectional"))
      (node (ref "C4") (pin "2") (pinfunction "2_2") (pintype "bidirectional"))
      (node (ref "C5") (pin "2") (pinfunction "2_2") (pintype "bidirectional"))
      (node (ref "C6") (pin "2") (pinfunction "2_2") (pintype "bidirectional"))
      (node (ref "C7") (pin "2") (pinfunction "2_2") (pintype "bidirectional"))
      (node (ref "C8") (pin "2") (pinfunction "2_2") (pintype "bidirectional"))
      (node (ref "C9") (pin "2") (pinfunction "2_2") (pintype "bidirectional"))
      (node (ref "D5") (pin "C") (pinfunction "CATHODE_C") (pintype "bidirectional"))
      (node (ref "J1") (pin "16") (pinfunction "16_16") (pintype "passive"))
      (node (ref "J1") (pin "20") (pinfunction "20_20") (pintype "passive"))
      (node (ref "J1") (pin "21") (pinfunction "21_21") (pintype "passive"))
      (node (ref "J1") (pin "24") (pinfunction "24_24") (pintype "passive"))
      (node (ref "J1") (pin "25") (pinfunction "25_25") (pintype "passive"))
      (node (ref "J1") (pin "6") (pinfunction "6_6") (pintype "passive"))
      (node (ref "J2") (pin "6") (pinfunction "GND_6") (pintype "bidirectional"))
      (node (ref "J2") (pin "B") (pinfunction "B_B") (pintype "bidirectional"))
      (node (ref "J2") (pin "MOUNT0") (pinfunction "GND_MOUNT0") (pintype "bidirectional"))
      (node (ref "J2") (pin "MOUNT1") (pinfunction "GND_MOUNT1") (pintype "bidirectional"))
      (node (ref "J2") (pin "MOUNT2") (pinfunction "GND_MOUNT2") (pintype "bidirectional"))
      (node (ref "J2") (pin "MOUNT3") (pinfunction "GND_MOUNT3") (pintype "bidirectional"))
      (node (ref "J3") (pin "4") (pinfunction "4_4") (pintype "bidirectional"))
      (node (ref "J4") (pin "4") (pinfunction "4_4") (pintype "bidirectional"))
      (node (ref "J5") (pin "4") (pinfunction "4_4") (pintype "bidirectional"))
      (node (ref "J6") (pin "GND@0") (pinfunction "GND_GND@0") (pintype "bidirectional"))
      (node (ref "J6") (pin "GND@1") (pinfunction "GND_GND@1") (pintype "bidirectional"))
      (node (ref "J6") (pin "GND@2") (pinfunction "GND_GND@2") (pintype "bidirectional"))
      (node (ref "J7") (pin "4") (pinfunction "4_4") (pintype "bidirectional"))
      (node (ref "S2") (pin "3") (pinfunction "P$2_3") (pintype "passive"))
      (node (ref "S2") (pin "4") (pinfunction "P$2_4") (pintype "passive"))
      (node (ref "S3") (pin "3") (pinfunction "P$2_3") (pintype "passive"))
      (node (ref "S3") (pin "4") (pinfunction "P$2_4") (pintype "passive"))
      (node (ref "S5") (pin "1") (pinfunction "A_1") (pintype "bidirectional"))
      (node (ref "TP37") (pin "TESTPOINT") (pinfunction "TESTPOINT_TESTPOINT") (pintype "bidirectional"))
      (node (ref "TP38") (pin "TESTPOINT") (pinfunction "TESTPOINT_TESTPOINT") (pintype "bidirectional"))
      (node (ref "TP39") (pin "TESTPOINT") (pinfunction "TESTPOINT_TESTPOINT") (pintype "bidirectional"))
      (node (ref "TP40") (pin "TESTPOINT") (pinfunction "TESTPOINT_TESTPOINT") (pintype "bidirectional"))
      (node (ref "TP41") (pin "TESTPOINT") (pinfunction "TESTPOINT_TESTPOINT") (pintype "bidirectional"))
      (node (ref "TP42") (pin "TESTPOINT") (pinfunction "TESTPOINT_TESTPOINT") (pintype "bidirectional"))
      (node (ref "TP43") (pin "1") (pinfunction "TESTPOINT_1") (pintype "bidirectional"))
      (node (ref "TP44") (pin "1") (pinfunction "TESTPOINT_1") (pintype "bidirectional"))
      (node (ref "U1") (pin "3") (pinfunction "GND_3") (pintype "bidirectional"))
      (node (ref "U1") (pin "5") (pinfunction "GND_5") (pintype "bidirectional"))
      (node (ref "U1") (pin "6") (pinfunction "GND_6") (pintype "bidirectional"))
      (node (ref "U1") (pin "7") (pinfunction "GND_7") (pintype "bidirectional"))
      (node (ref "U2") (pin "2") (pinfunction "GND_2") (pintype "bidirectional"))
      (node (ref "U2") (pin "3") (pinfunction "A0_3") (pintype "bidirectional"))
      (node (ref "U2") (pin "EP") (pinfunction "GND_EP") (pintype "bidirectional"))
      (node (ref "U3") (pin "11") (pinfunction "FSYNC_11") (pintype "bidirectional"))
      (node (ref "U3") (pin "18") (pinfunction "GND_18") (pintype "bidirectional"))
      (node (ref "U3") (pin "20") (pinfunction "GND_20") (pintype "bidirectional"))
      (node (ref "U3") (pin "9") (pinfunction "AD0/MISO_9") (pintype "bidirectional"))
      (node (ref "U4") (pin "4") (pinfunction "GND_4") (pintype "bidirectional"))
      (node (ref "U5") (pin "2") (pinfunction "GND_2") (pintype "bidirectional"))
      (node (ref "U6") (pin "4") (pinfunction "GND_4") (pintype "bidirectional"))
    )
    (net (code "7") (name "GROVE_A0") (class "Default")
      (node (ref "J5") (pin "1") (pinfunction "1_1") (pintype "bidirectional"))
      (node (ref "J6") (pin "P0.04") (pinfunction "P0.04/AIN2_P0.04") (pintype "bidirectional"))
      (node (ref "TP9") (pin "TESTPOINT") (pinfunction "TESTPOINT_TESTPOINT") (pintype "bidirectional"))
    )
    (net (code "8") (name "GROVE_A1") (class "Default")
      (node (ref "J5") (pin "2") (pinfunction "2_2") (pintype "bidirectional"))
      (node (ref "J6") (pin "P0.03") (pinfunction "P0.03/AIN1_P0.03") (pintype "bidirectional"))
      (node (ref "TP10") (pin "TESTPOINT") (pinfunction "TESTPOINT_TESTPOINT") (pintype "bidirectional"))
    )
    (net (code "9") (name "GROVE_D0") (class "Default")
      (node (ref "J6") (pin "P0.02") (pinfunction "P0.02/AIN0_P0.02") (pintype "bidirectional"))
      (node (ref "J7") (pin "1") (pinfunction "1_1") (pintype "bidirectional"))
      (node (ref "TP27") (pin "TESTPOINT") (pinfunction "TESTPOINT_TESTPOINT") (pintype "bidirectional"))
    )
    (net (code "10") (name "GROVE_D1") (class "Default")
      (node (ref "J6") (pin "P0.05") (pinfunction "P0.05/AIN3_P0.05") (pintype "bidirectional"))
      (node (ref "J7") (pin "2") (pinfunction "2_2") (pintype "bidirectional"))
      (node (ref "TP22") (pin "TESTPOINT") (pinfunction "TESTPOINT_TESTPOINT") (pintype "bidirectional"))
    )
    (net (code "11") (name "LCD_MISO") (class "Default")
      (node (ref "A1") (pin "13") (pinfunction "MISO_13") (pintype "bidirectional"))
      (node (ref "J6") (pin "P0.16") (pinfunction "P0.16_P0.16") (pintype "bidirectional"))
      (node (ref "TP17") (pin "TESTPOINT") (pinfunction "TESTPOINT_TESTPOINT") (pintype "bidirectional"))
    )
    (net (code "12") (name "LCD_MOSI") (class "Default")
      (node (ref "A1") (pin "14") (pinfunction "MOSI_14") (pintype "bidirectional"))
      (node (ref "J6") (pin "P0.15") (pinfunction "P0.15_P0.15") (pintype "bidirectional"))
      (node (ref "TP15") (pin "TESTPOINT") (pinfunction "TESTPOINT_TESTPOINT") (pintype "bidirectional"))
    )
    (net (code "13") (name "LCD_SCLK") (class "Default")
      (node (ref "A1") (pin "12") (pinfunction "SCLK_12") (pintype "bidirectional"))
      (node (ref "J6") (pin "P0.17") (pinfunction "P0.17_P0.17") (pintype "bidirectional"))
      (node (ref "TP19") (pin "TESTPOINT") (pinfunction "TESTPOINT_TESTPOINT") (pintype "bidirectional"))
    )
    (net (code "14") (name "Net-(D1-ANODE)") (class "Default")
      (node (ref "D1") (pin "P$2") (pinfunction "ANODE_P$2") (pintype "bidirectional"))
      (node (ref "J1") (pin "8") (pinfunction "8_8") (pintype "passive"))
      (node (ref "J1") (pin "9") (pinfunction "9_9") (pintype "passive"))
    )
    (net (code "15") (name "Net-(D2-ANODE)") (class "Default")
      (node (ref "D2") (pin "A") (pinfunction "ANODE_A") (pintype "bidirectional"))
      (node (ref "R1") (pin "2") (pinfunction "2_2") (pintype "passive"))
    )
    (net (code "16") (name "Net-(D3-ANODE)") (class "Default")
      (node (ref "D3") (pin "A") (pinfunction "ANODE_A") (pintype "bidirectional"))
      (node (ref "R2") (pin "2") (pinfunction "2_2") (pintype "passive"))
    )
    (net (code "17") (name "Net-(D4-ANODE)") (class "Default")
      (node (ref "D4") (pin "A") (pinfunction "ANODE_A") (pintype "bidirectional"))
      (node (ref "R3") (pin "2") (pinfunction "2_2") (pintype "passive"))
    )
    (net (code "18") (name "Net-(D5-ANODE)") (class "Default")
      (node (ref "D5") (pin "A") (pinfunction "ANODE_A") (pintype "bidirectional"))
      (node (ref "R4") (pin "2") (pinfunction "2_2") (pintype "passive"))
    )
    (net (code "19") (name "Net-(J2-VCC)") (class "Default")
      (node (ref "C11") (pin "1") (pinfunction "1_1") (pintype "bidirectional"))
      (node (ref "J2") (pin "4") (pinfunction "VCC_4") (pintype "bidirectional"))
      (node (ref "R15") (pin "2") (pinfunction "2_2") (pintype "passive"))
      (node (ref "R7") (pin "2") (pinfunction "2_2") (pintype "passive"))
      (node (ref "R8") (pin "2") (pinfunction "2_2") (pintype "passive"))
      (node (ref "R9") (pin "2") (pinfunction "2_2") (pintype "passive"))
      (node (ref "U6") (pin "1") (pinfunction "VLOAD_1") (pintype "bidirectional"))
      (node (ref "U6") (pin "2") (pinfunction "VLOAD_2") (pintype "bidirectional"))
    )
    (net (code "20") (name "Net-(J6-P0.21{slash}RESET)") (class "Default")
      (node (ref "J6") (pin "P0.21") (pinfunction "P0.21/RESET_P0.21") (pintype "bidirectional"))
      (node (ref "R10") (pin "1") (pinfunction "1_1") (pintype "passive"))
      (node (ref "S2") (pin "1") (pinfunction "P$1_1") (pintype "passive"))
      (node (ref "S2") (pin "2") (pinfunction "P$1_2") (pintype "passive"))
      (node (ref "TP11") (pin "TESTPOINT") (pinfunction "TESTPOINT_TESTPOINT") (pintype "bidirectional"))
    )
    (net (code "21") (name "Net-(S1-P$1)") (class "Default")
      (node (ref "S1") (pin "1") (pinfunction "P$1_1") (pintype "passive"))
      (node (ref "U1") (pin "2") (pinfunction "ST_2") (pintype "bidirectional"))
    )
    (net (code "22") (name "Net-(U3-REGOUT)") (class "Default")
      (node (ref "C2") (pin "1") (pinfunction "1_1") (pintype "bidirectional"))
      (node (ref "U3") (pin "10") (pinfunction "REGOUT_10") (pintype "bidirectional"))
    )
    (net (code "23") (name "SD_ENABLE") (class "Default")
      (node (ref "J6") (pin "P0.26") (pinfunction "P0.26_P0.26") (pintype "bidirectional"))
      (node (ref "R16") (pin "1") (pinfunction "1_1") (pintype "passive"))
      (node (ref "TP28") (pin "TESTPOINT") (pinfunction "TESTPOINT_TESTPOINT") (pintype "bidirectional"))
      (node (ref "U6") (pin "3") (pinfunction "EN_3") (pintype "bidirectional"))
    )
    (net (code "24") (name "SD_MISO") (class "Default")
      (node (ref "J2") (pin "7") (pinfunction "DATA0/MISO_7") (pintype "bidirectional"))
      (node (ref "J6") (pin "P0.12") (pinfunction "P0.12_P0.12") (pintype "bidirectional"))
      (node (ref "R9") (pin "1") (pinfunction "1_1") (pintype "passive"))
      (node (ref "TP18") (pin "TESTPOINT") (pinfunction "TESTPOINT_TESTPOINT") (pintype "bidirectional"))
    )
    (net (code "25") (name "SD_MOSI") (class "Default")
      (node (ref "J2") (pin "3") (pinfunction "CMD/MOSI_3") (pintype "bidirectional"))
      (node (ref "J6") (pin "P0.11") (pinfunction "P0.11_P0.11") (pintype "bidirectional"))
      (node (ref "R7") (pin "1") (pinfunction "1_1") (pintype "passive"))
      (node (ref "TP16") (pin "TESTPOINT") (pinfunction "TESTPOINT_TESTPOINT") (pintype "bidirectional"))
    )
    (net (code "26") (name "SD_SCLK") (class "Default")
      (node (ref "J2") (pin "5") (pinfunction "CLK_5") (pintype "bidirectional"))
      (node (ref "J6") (pin "P0.13") (pinfunction "P0.13_P0.13") (pintype "bidirectional"))
      (node (ref "TP20") (pin "TESTPOINT") (pinfunction "TESTPOINT_TESTPOINT") (pintype "bidirectional"))
    )
    (net (code "27") (name "SENSORS_SCL") (class "Default")
      (node (ref "J3") (pin "1") (pinfunction "1_1") (pintype "bidirectional"))
      (node (ref "J6") (pin "P0.19") (pinfunction "P0.19_P0.19") (pintype "bidirectional"))
      (node (ref "R11") (pin "1") (pinfunction "1_1") (pintype "passive"))
      (node (ref "TP23") (pin "TESTPOINT") (pinfunction "TESTPOINT_TESTPOINT") (pintype "bidirectional"))
      (node (ref "U2") (pin "5") (pinfunction "SCL_5") (pintype "bidirectional"))
      (node (ref "U3") (pin "23") (pinfunction "SCLK_23") (pintype "bidirectional"))
      (node (ref "U4") (pin "3") (pinfunction "SCL_3") (pintype "bidirectional"))
      (node (ref "U5") (pin "6") (pinfunction "SCL_6") (pintype "bidirectional"))
    )
    (net (code "28") (name "SENSORS_SDA") (class "Default")
      (node (ref "J3") (pin "2") (pinfunction "2_2") (pintype "bidirectional"))
      (node (ref "J6") (pin "P0.20") (pinfunction "P0.20_P0.20") (pintype "bidirectional"))
      (node (ref "R12") (pin "1") (pinfunction "1_1") (pintype "passive"))
      (node (ref "TP24") (pin "TESTPOINT") (pinfunction "TESTPOINT_TESTPOINT") (pintype "bidirectional"))
      (node (ref "U2") (pin "6") (pinfunction "SDA_6") (pintype "bidirectional"))
      (node (ref "U3") (pin "24") (pinfunction "SDA/MOSI_24") (pintype "bidirectional"))
      (node (ref "U4") (pin "2") (pinfunction "SDA_2") (pintype "bidirectional"))
      (node (ref "U5") (pin "1") (pinfunction "SDA_1") (pintype "bidirectional"))
    )
    (net (code "29") (name "SWITCH_0") (class "Default")
      (node (ref "J6") (pin "P0.22") (pinfunction "P0.22_P0.22") (pintype "bidirectional"))
      (node (ref "S5") (pin "IN") (pinfunction "IN_IN") (pintype "bidirectional"))
      (node (ref "TP31") (pin "TESTPOINT") (pinfunction "TESTPOINT_TESTPOINT") (pintype "bidirectional"))
    )
    (net (code "30") (name "UART_RX") (class "Default")
      (node (ref "J1") (pin "1") (pinfunction "1_1") (pintype "passive"))
      (node (ref "J4") (pin "2") (pinfunction "2_2") (pintype "bidirectional"))
      (node (ref "J6") (pin "P0.08") (pinfunction "P0.08_P0.08") (pintype "bidirectional"))
      (node (ref "TP25") (pin "TESTPOINT") (pinfunction "TESTPOINT_TESTPOINT") (pintype "bidirectional"))
    )
    (net (code "31") (name "UART_TX") (class "Default")
      (node (ref "J1") (pin "2") (pinfunction "2_2") (pintype "passive"))
      (node (ref "J4") (pin "1") (pinfunction "1_1") (pintype "bidirectional"))
      (node (ref "J6") (pin "P0.06") (pinfunction "P0.06_P0.06") (pintype "bidirectional"))
      (node (ref "TP26") (pin "TESTPOINT") (pinfunction "TESTPOINT_TESTPOINT") (pintype "bidirectional"))
    )
    (net (code "32") (name "unconnected-(J1-Pad3)") (class "Default")
      (node (ref "J1") (pin "3") (pinfunction "3_3") (pintype "passive"))
    )
    (net (code "33") (name "unconnected-(J1-Pad4)") (class "Default")
      (node (ref "J1") (pin "4") (pinfunction "4_4") (pintype "passive"))
    )
    (net (code "34") (name "unconnected-(J1-Pad5)") (class "Default")
      (node (ref "J1") (pin "5") (pinfunction "5_5") (pintype "passive"))
    )
    (net (code "35") (name "unconnected-(J1-Pad7)") (class "Default")
      (node (ref "J1") (pin "7") (pinfunction "7_7") (pintype "passive"))
    )
    (net (code "36") (name "unconnected-(J1-Pad10)") (class "Default")
      (node (ref "J1") (pin "10") (pinfunction "10_10") (pintype "passive"))
    )
    (net (code "37") (name "unconnected-(J1-Pad11)") (class "Default")
      (node (ref "J1") (pin "11") (pinfunction "11_11") (pintype "passive"))
    )
    (net (code "38") (name "unconnected-(J1-Pad12)") (class "Default")
      (node (ref "J1") (pin "12") (pinfunction "12_12") (pintype "passive"))
    )
    (net (code "39") (name "unconnected-(J1-Pad13)") (class "Default")
      (node (ref "J1") (pin "13") (pinfunction "13_13") (pintype "passive"))
    )
    (net (code "40") (name "unconnected-(J1-Pad14)") (class "Default")
      (node (ref "J1") (pin "14") (pinfunction "14_14") (pintype "passive"))
    )
    (net (code "41") (name "unconnected-(J1-Pad15)") (class "Default")
      (node (ref "J1") (pin "15") (pinfunction "15_15") (pintype "passive"))
    )
    (net (code "42") (name "unconnected-(J1-Pad17)") (class "Default")
      (node (ref "J1") (pin "17") (pinfunction "17_17") (pintype "passive"))
    )
    (net (code "43") (name "unconnected-(J1-Pad18)") (class "Default")
      (node (ref "J1") (pin "18") (pinfunction "18_18") (pintype "passive"))
    )
    (net (code "44") (name "unconnected-(J1-Pad19)") (class "Default")
      (node (ref "J1") (pin "19") (pinfunction "19_19") (pintype "passive"))
    )
    (net (code "45") (name "unconnected-(J1-Pad22)") (class "Default")
      (node (ref "J1") (pin "22") (pinfunction "22_22") (pintype "passive"))
    )
    (net (code "46") (name "unconnected-(J1-Pad23)") (class "Default")
      (node (ref "J1") (pin "23") (pinfunction "23_23") (pintype "passive"))
    )
    (net (code "47") (name "unconnected-(J2-DATA1{slash}RSV-Pad8)") (class "Default")
      (node (ref "J2") (pin "8") (pinfunction "DATA1/RSV_8") (pintype "bidirectional"))
    )
    (net (code "48") (name "unconnected-(J2-DATA2{slash}NC-Pad1)") (class "Default")
      (node (ref "J2") (pin "1") (pinfunction "DATA2/NC_1") (pintype "bidirectional"))
    )
    (net (code "49") (name "unconnected-(U3-AUX_CL-Pad7)") (class "Default")
      (node (ref "U3") (pin "7") (pinfunction "AUX_CL_7") (pintype "bidirectional"))
    )
    (net (code "50") (name "unconnected-(U3-AUX_DA-Pad21)") (class "Default")
      (node (ref "U3") (pin "21") (pinfunction "AUX_DA_21") (pintype "bidirectional"))
    )
    (net (code "51") (name "~{BUTTON_0}") (class "Default")
      (node (ref "J6") (pin "P0.28") (pinfunction "P0.28/AIN4_P0.28") (pintype "bidirectional"))
      (node (ref "R13") (pin "1") (pinfunction "1_1") (pintype "passive"))
      (node (ref "S3") (pin "1") (pinfunction "P$1_1") (pintype "passive"))
      (node (ref "S3") (pin "2") (pinfunction "P$1_2") (pintype "passive"))
      (node (ref "TP29") (pin "TESTPOINT") (pinfunction "TESTPOINT_TESTPOINT") (pintype "bidirectional"))
    )
    (net (code "52") (name "~{IMU_INTERRUPT}") (class "Default")
      (node (ref "J6") (pin "P0.07") (pinfunction "P0.07_P0.07") (pintype "bidirectional"))
      (node (ref "R6") (pin "1") (pinfunction "1_1") (pintype "passive"))
      (node (ref "TP1") (pin "TESTPOINT") (pinfunction "TESTPOINT_TESTPOINT") (pintype "bidirectional"))
      (node (ref "U3") (pin "12") (pinfunction "INT_12") (pintype "bidirectional"))
    )
    (net (code "53") (name "~{LCD_CS}") (class "Default")
      (node (ref "A1") (pin "16") (pinfunction "~{CS}_16") (pintype "bidirectional"))
      (node (ref "J6") (pin "P0.18") (pinfunction "P0.18_P0.18") (pintype "bidirectional"))
      (node (ref "TP3") (pin "TESTPOINT") (pinfunction "TESTPOINT_TESTPOINT") (pintype "bidirectional"))
    )
    (net (code "54") (name "~{LED_0}") (class "Default")
      (node (ref "D2") (pin "C") (pinfunction "CATHODE_C") (pintype "bidirectional"))
      (node (ref "J6") (pin "P0.25") (pinfunction "P0.25_P0.25") (pintype "bidirectional"))
      (node (ref "TP6") (pin "TESTPOINT") (pinfunction "TESTPOINT_TESTPOINT") (pintype "bidirectional"))
    )
    (net (code "55") (name "~{LED_1}") (class "Default")
      (node (ref "D3") (pin "C") (pinfunction "CATHODE_C") (pintype "bidirectional"))
      (node (ref "J6") (pin "P0.24") (pinfunction "P0.24_P0.24") (pintype "bidirectional"))
      (node (ref "TP7") (pin "TESTPOINT") (pinfunction "TESTPOINT_TESTPOINT") (pintype "bidirectional"))
    )
    (net (code "56") (name "~{LED_2}") (class "Default")
      (node (ref "D4") (pin "C") (pinfunction "CATHODE_C") (pintype "bidirectional"))
      (node (ref "J6") (pin "P0.23") (pinfunction "P0.23_P0.23") (pintype "bidirectional"))
      (node (ref "TP8") (pin "TESTPOINT") (pinfunction "TESTPOINT_TESTPOINT") (pintype "bidirectional"))
    )
    (net (code "57") (name "~{LIGHT_INTERRUPT}") (class "Default")
      (node (ref "J6") (pin "P0.27") (pinfunction "P0.27_P0.27") (pintype "bidirectional"))
      (node (ref "R5") (pin "1") (pinfunction "1_1") (pintype "passive"))
      (node (ref "TP2") (pin "TESTPOINT") (pinfunction "TESTPOINT_TESTPOINT") (pintype "bidirectional"))
      (node (ref "U2") (pin "4") (pinfunction "~{INT}_4") (pintype "bidirectional"))
    )
    (net (code "58") (name "~{SD_CS}") (class "Default")
      (node (ref "J2") (pin "2") (pinfunction "DATA3-CD/CS_N_2") (pintype "bidirectional"))
      (node (ref "J6") (pin "P0.14") (pinfunction "P0.14_P0.14") (pintype "bidirectional"))
      (node (ref "R8") (pin "1") (pinfunction "1_1") (pintype "passive"))
      (node (ref "TP4") (pin "TESTPOINT") (pinfunction "TESTPOINT_TESTPOINT") (pintype "bidirectional"))
    )
    (net (code "59") (name "~{SD_DETECT}") (class "Default")
      (node (ref "J2") (pin "A") (pinfunction "A_A") (pintype "bidirectional"))
      (node (ref "R15") (pin "1") (pinfunction "1_1") (pintype "passive"))
      (node (ref "TP5") (pin "TESTPOINT") (pinfunction "TESTPOINT_TESTPOINT") (pintype "bidirectional"))
    )
  )
)
